# OpAmp_CH4.net
KiCad netlist of a schematic drawn in Altium Designer
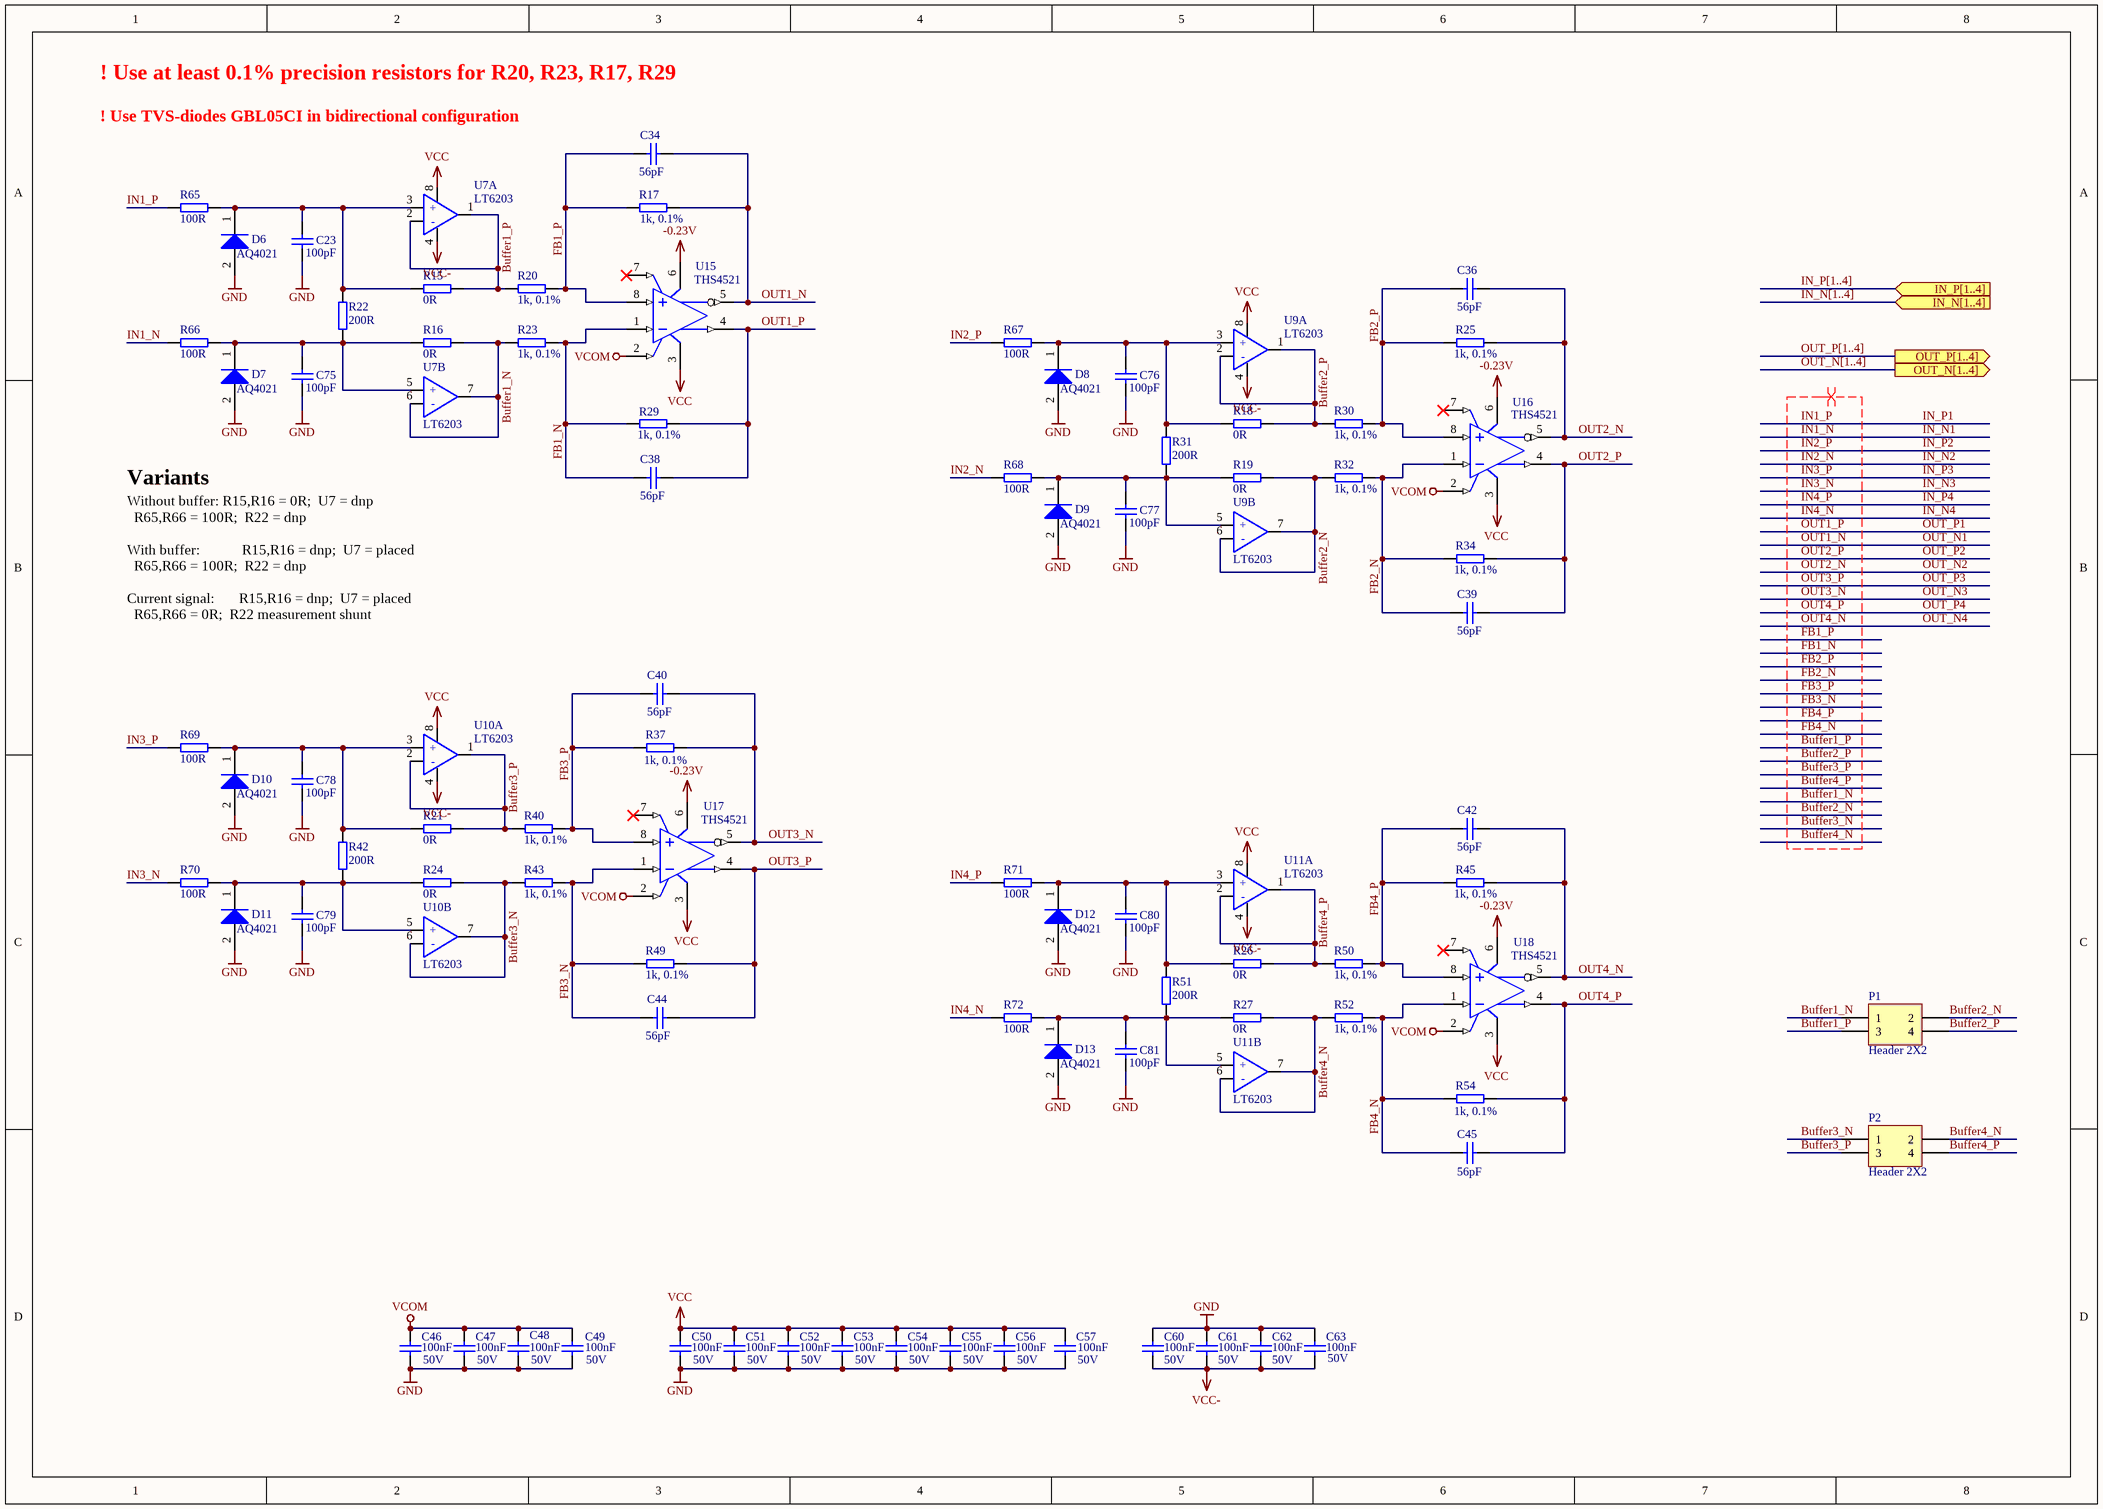
[diagram p0: OpAmp_CH4.SchDoc]

(export (version "E")
  (design (tool "Eeschema 10.0.6"))
  (components
    (comp (ref "C23")
      (value "100pF")
      (footprint "CAPC1608X07N")
      (fields
        (field (name "MF") "Würth Elektronik")
        (field (name "MPN") "885012006057")
        (field (name "VOLTAGE") "50V")
      )
      (libsource (lib "UltraZohm_ADC") (part "Cap_0603"))
    )
    (comp (ref "C34")
      (value "56pF")
      (footprint "CAPC1608X07N")
      (fields
        (field (name "MF") "Vishay")
        (field (name "MPN") "VJ0603A560JXACW1BC")
        (field (name "VOLTAGE") "50V")
      )
      (libsource (lib "UltraZohm_ADC") (part "Cap_0603"))
    )
    (comp (ref "C36")
      (value "56pF")
      (footprint "CAPC1608X07N")
      (fields
        (field (name "MF") "Vishay")
        (field (name "MPN") "VJ0603A560JXACW1BC")
        (field (name "VOLTAGE") "50V")
      )
      (libsource (lib "UltraZohm_ADC") (part "Cap_0603"))
    )
    (comp (ref "C38")
      (value "56pF")
      (footprint "CAPC1608X07N")
      (fields
        (field (name "MF") "Vishay")
        (field (name "MPN") "VJ0603A560JXACW1BC")
        (field (name "VOLTAGE") "50V")
      )
      (libsource (lib "UltraZohm_ADC") (part "Cap_0603"))
    )
    (comp (ref "C39")
      (value "56pF")
      (footprint "CAPC1608X07N")
      (fields
        (field (name "MF") "Vishay")
        (field (name "MPN") "VJ0603A560JXACW1BC")
        (field (name "VOLTAGE") "50V")
      )
      (libsource (lib "UltraZohm_ADC") (part "Cap_0603"))
    )
    (comp (ref "C40")
      (value "56pF")
      (footprint "CAPC1608X07N")
      (fields
        (field (name "MF") "Vishay")
        (field (name "MPN") "VJ0603A560JXACW1BC")
        (field (name "VOLTAGE") "50V")
      )
      (libsource (lib "UltraZohm_ADC") (part "Cap_0603"))
    )
    (comp (ref "C42")
      (value "56pF")
      (footprint "CAPC1608X07N")
      (fields
        (field (name "MF") "Vishay")
        (field (name "MPN") "VJ0603A560JXACW1BC")
        (field (name "VOLTAGE") "50V")
      )
      (libsource (lib "UltraZohm_ADC") (part "Cap_0603"))
    )
    (comp (ref "C44")
      (value "56pF")
      (footprint "CAPC1608X07N")
      (fields
        (field (name "MF") "Vishay")
        (field (name "MPN") "VJ0603A560JXACW1BC")
        (field (name "VOLTAGE") "50V")
      )
      (libsource (lib "UltraZohm_ADC") (part "Cap_0603"))
    )
    (comp (ref "C45")
      (value "56pF")
      (footprint "CAPC1608X07N")
      (fields
        (field (name "MF") "Vishay")
        (field (name "MPN") "VJ0603A560JXACW1BC")
        (field (name "VOLTAGE") "50V")
      )
      (libsource (lib "UltraZohm_ADC") (part "Cap_0603"))
    )
    (comp (ref "C46")
      (value "100nF")
      (footprint "CAPC1608X07N")
      (fields
        (field (name "MF") "Yageo")
        (field (name "MPN") "CC0603KRX7R9BB104")
        (field (name "VOLTAGE") "50V")
      )
      (libsource (lib "UltraZohm_ADC") (part "Cap_0603"))
    )
    (comp (ref "C47")
      (value "100nF")
      (footprint "CAPC1608X07N")
      (fields
        (field (name "MF") "Yageo")
        (field (name "MPN") "CC0603KRX7R9BB104")
        (field (name "VOLTAGE") "50V")
      )
      (libsource (lib "UltraZohm_ADC") (part "Cap_0603"))
    )
    (comp (ref "C48")
      (value "100nF")
      (footprint "CAPC1608X07N")
      (fields
        (field (name "MF") "Yageo")
        (field (name "MPN") "CC0603KRX7R9BB104")
        (field (name "VOLTAGE") "50V")
      )
      (libsource (lib "UltraZohm_ADC") (part "Cap_0603"))
    )
    (comp (ref "C49")
      (value "100nF")
      (footprint "CAPC1608X07N")
      (fields
        (field (name "MF") "Yageo")
        (field (name "MPN") "CC0603KRX7R9BB104")
        (field (name "VOLTAGE") "50V")
      )
      (libsource (lib "UltraZohm_ADC") (part "Cap_0603"))
    )
    (comp (ref "C50")
      (value "100nF")
      (footprint "CAPC1608X07N")
      (fields
        (field (name "MF") "Yageo")
        (field (name "MPN") "CC0603KRX7R9BB104")
        (field (name "VOLTAGE") "50V")
      )
      (libsource (lib "UltraZohm_ADC") (part "Cap_0603"))
    )
    (comp (ref "C51")
      (value "100nF")
      (footprint "CAPC1608X07N")
      (fields
        (field (name "MF") "Yageo")
        (field (name "MPN") "CC0603KRX7R9BB104")
        (field (name "VOLTAGE") "50V")
      )
      (libsource (lib "UltraZohm_ADC") (part "Cap_0603"))
    )
    (comp (ref "C52")
      (value "100nF")
      (footprint "CAPC1608X07N")
      (fields
        (field (name "MF") "Yageo")
        (field (name "MPN") "CC0603KRX7R9BB104")
        (field (name "VOLTAGE") "50V")
      )
      (libsource (lib "UltraZohm_ADC") (part "Cap_0603"))
    )
    (comp (ref "C53")
      (value "100nF")
      (footprint "CAPC1608X07N")
      (fields
        (field (name "MF") "Yageo")
        (field (name "MPN") "CC0603KRX7R9BB104")
        (field (name "VOLTAGE") "50V")
      )
      (libsource (lib "UltraZohm_ADC") (part "Cap_0603"))
    )
    (comp (ref "C54")
      (value "100nF")
      (footprint "CAPC1608X07N")
      (fields
        (field (name "MF") "Yageo")
        (field (name "MPN") "CC0603KRX7R9BB104")
        (field (name "VOLTAGE") "50V")
      )
      (libsource (lib "UltraZohm_ADC") (part "Cap_0603"))
    )
    (comp (ref "C55")
      (value "100nF")
      (footprint "CAPC1608X07N")
      (fields
        (field (name "MF") "Yageo")
        (field (name "MPN") "CC0603KRX7R9BB104")
        (field (name "VOLTAGE") "50V")
      )
      (libsource (lib "UltraZohm_ADC") (part "Cap_0603"))
    )
    (comp (ref "C56")
      (value "100nF")
      (footprint "CAPC1608X07N")
      (fields
        (field (name "MF") "Yageo")
        (field (name "MPN") "CC0603KRX7R9BB104")
        (field (name "VOLTAGE") "50V")
      )
      (libsource (lib "UltraZohm_ADC") (part "Cap_0603"))
    )
    (comp (ref "C57")
      (value "100nF")
      (footprint "CAPC1608X07N")
      (fields
        (field (name "MF") "Yageo")
        (field (name "MPN") "CC0603KRX7R9BB104")
        (field (name "VOLTAGE") "50V")
      )
      (libsource (lib "UltraZohm_ADC") (part "Cap_0603"))
    )
    (comp (ref "C60")
      (value "100nF")
      (footprint "CAPC1608X07N")
      (fields
        (field (name "MF") "Yageo")
        (field (name "MPN") "CC0603KRX7R9BB104")
        (field (name "VOLTAGE") "50V")
      )
      (libsource (lib "UltraZohm_ADC") (part "Cap_0603"))
    )
    (comp (ref "C61")
      (value "100nF")
      (footprint "CAPC1608X07N")
      (fields
        (field (name "MF") "Yageo")
        (field (name "MPN") "CC0603KRX7R9BB104")
        (field (name "VOLTAGE") "50V")
      )
      (libsource (lib "UltraZohm_ADC") (part "Cap_0603"))
    )
    (comp (ref "C62")
      (value "100nF")
      (footprint "CAPC1608X07N")
      (fields
        (field (name "MF") "Yageo")
        (field (name "MPN") "CC0603KRX7R9BB104")
        (field (name "VOLTAGE") "50V")
      )
      (libsource (lib "UltraZohm_ADC") (part "Cap_0603"))
    )
    (comp (ref "C63")
      (value "100nF")
      (footprint "CAPC1608X07N")
      (fields
        (field (name "MF") "Yageo")
        (field (name "MPN") "CC0603KRX7R9BB104")
        (field (name "VOLTAGE") "50V")
      )
      (libsource (lib "UltraZohm_ADC") (part "Cap_0603"))
    )
    (comp (ref "C75")
      (value "100pF")
      (footprint "CAPC1608X07N")
      (fields
        (field (name "MF") "Würth Elektronik")
        (field (name "MPN") "885012006057")
        (field (name "VOLTAGE") "50V")
      )
      (libsource (lib "UltraZohm_ADC") (part "Cap_0603"))
    )
    (comp (ref "C76")
      (value "100pF")
      (footprint "CAPC1608X07N")
      (fields
        (field (name "MF") "Würth Elektronik")
        (field (name "MPN") "885012006057")
        (field (name "VOLTAGE") "50V")
      )
      (libsource (lib "UltraZohm_ADC") (part "Cap_0603"))
    )
    (comp (ref "C77")
      (value "100pF")
      (footprint "CAPC1608X07N")
      (fields
        (field (name "MF") "Würth Elektronik")
        (field (name "MPN") "885012006057")
        (field (name "VOLTAGE") "50V")
      )
      (libsource (lib "UltraZohm_ADC") (part "Cap_0603"))
    )
    (comp (ref "C78")
      (value "100pF")
      (footprint "CAPC1608X07N")
      (fields
        (field (name "MF") "Würth Elektronik")
        (field (name "MPN") "885012006057")
        (field (name "VOLTAGE") "50V")
      )
      (libsource (lib "UltraZohm_ADC") (part "Cap_0603"))
    )
    (comp (ref "C79")
      (value "100pF")
      (footprint "CAPC1608X07N")
      (fields
        (field (name "MF") "Würth Elektronik")
        (field (name "MPN") "885012006057")
        (field (name "VOLTAGE") "50V")
      )
      (libsource (lib "UltraZohm_ADC") (part "Cap_0603"))
    )
    (comp (ref "C80")
      (value "100pF")
      (footprint "CAPC1608X07N")
      (fields
        (field (name "MF") "Würth Elektronik")
        (field (name "MPN") "885012006057")
        (field (name "VOLTAGE") "50V")
      )
      (libsource (lib "UltraZohm_ADC") (part "Cap_0603"))
    )
    (comp (ref "C81")
      (value "100pF")
      (footprint "CAPC1608X07N")
      (fields
        (field (name "MF") "Würth Elektronik")
        (field (name "MPN") "885012006057")
        (field (name "VOLTAGE") "50V")
      )
      (libsource (lib "UltraZohm_ADC") (part "Cap_0603"))
    )
    (comp (ref "D6")
      (value "AQ4021")
      (footprint "SOD-323_SuppressorDiode")
      (description "ESD Suppressor Diode TVS Bi-Dir 5V")
      (fields (field (name "MF") "Littelfuse") (field (name "MPN") "AQ4021-01FTG-C"))
      (libsource (lib "UltraZohm_ADC") (part "GBLCxx"))
    )
    (comp (ref "D7")
      (value "AQ4021")
      (footprint "SOD-323_SuppressorDiode")
      (description "ESD Suppressor Diode TVS Bi-Dir 5V")
      (fields (field (name "MF") "Littelfuse") (field (name "MPN") "AQ4021-01FTG-C"))
      (libsource (lib "UltraZohm_ADC") (part "GBLCxx"))
    )
    (comp (ref "D8")
      (value "AQ4021")
      (footprint "SOD-323_SuppressorDiode")
      (description "ESD Suppressor Diode TVS Bi-Dir 5V")
      (fields (field (name "MF") "Littelfuse") (field (name "MPN") "AQ4021-01FTG-C"))
      (libsource (lib "UltraZohm_ADC") (part "GBLCxx"))
    )
    (comp (ref "D9")
      (value "AQ4021")
      (footprint "SOD-323_SuppressorDiode")
      (description "ESD Suppressor Diode TVS Bi-Dir 5V")
      (fields (field (name "MF") "Littelfuse") (field (name "MPN") "AQ4021-01FTG-C"))
      (libsource (lib "UltraZohm_ADC") (part "GBLCxx"))
    )
    (comp (ref "D10")
      (value "AQ4021")
      (footprint "SOD-323_SuppressorDiode")
      (description "ESD Suppressor Diode TVS Bi-Dir 5V")
      (fields (field (name "MF") "Littelfuse") (field (name "MPN") "AQ4021-01FTG-C"))
      (libsource (lib "UltraZohm_ADC") (part "GBLCxx"))
    )
    (comp (ref "D11")
      (value "AQ4021")
      (footprint "SOD-323_SuppressorDiode")
      (description "ESD Suppressor Diode TVS Bi-Dir 5V")
      (fields (field (name "MF") "Littelfuse") (field (name "MPN") "AQ4021-01FTG-C"))
      (libsource (lib "UltraZohm_ADC") (part "GBLCxx"))
    )
    (comp (ref "D12")
      (value "AQ4021")
      (footprint "SOD-323_SuppressorDiode")
      (description "ESD Suppressor Diode TVS Bi-Dir 5V")
      (fields (field (name "MF") "Littelfuse") (field (name "MPN") "AQ4021-01FTG-C"))
      (libsource (lib "UltraZohm_ADC") (part "GBLCxx"))
    )
    (comp (ref "D13")
      (value "AQ4021")
      (footprint "SOD-323_SuppressorDiode")
      (description "ESD Suppressor Diode TVS Bi-Dir 5V")
      (fields (field (name "MF") "Littelfuse") (field (name "MPN") "AQ4021-01FTG-C"))
      (libsource (lib "UltraZohm_ADC") (part "GBLCxx"))
    )
    (comp (ref "P1")
      (value "Header 2X2")
      (footprint "HDR2X2")
      (description "Header, 2-Pin, Dual row")
      (fields (field (name "PUBLISHER") "Altium Limited"))
      (libsource (lib "Miscellaneous Connectors") (part "Header 2X2"))
    )
    (comp (ref "P2")
      (value "Header 2X2")
      (footprint "HDR2X2")
      (description "Header, 2-Pin, Dual row")
      (fields (field (name "PUBLISHER") "Altium Limited"))
      (libsource (lib "Miscellaneous Connectors") (part "Header 2X2"))
    )
    (comp (ref "R15")
      (value "0R")
      (footprint "RESC1608X06N")
      (fields (field (name "MF") "Vishay / Dale") (field (name "MPN") "CRCW06030000Z0EBC"))
      (libsource (lib "UltraZohm_ADC") (part "R_0603"))
    )
    (comp (ref "R16")
      (value "0R")
      (footprint "RESC1608X06N")
      (fields (field (name "MF") "Vishay / Dale") (field (name "MPN") "CRCW06030000Z0EBC"))
      (libsource (lib "UltraZohm_ADC") (part "R_0603"))
    )
    (comp (ref "R17")
      (value "1k, 0.1%")
      (footprint "RESC1608X06N")
      (description "Precision Resistor 1k 0.1% 0603")
      (fields (field (name "MF") "IRC/TT Electronics") (field (name "MPN") "PCF-W0603LF-03-1001-B-P-LT"))
      (libsource (lib "UltraZohm_ADC") (part "R_0603"))
    )
    (comp (ref "R18")
      (value "0R")
      (footprint "RESC1608X06N")
      (fields (field (name "MF") "Vishay / Dale") (field (name "MPN") "CRCW06030000Z0EBC"))
      (libsource (lib "UltraZohm_ADC") (part "R_0603"))
    )
    (comp (ref "R19")
      (value "0R")
      (footprint "RESC1608X06N")
      (fields (field (name "MF") "Vishay / Dale") (field (name "MPN") "CRCW06030000Z0EBC"))
      (libsource (lib "UltraZohm_ADC") (part "R_0603"))
    )
    (comp (ref "R20")
      (value "1k, 0.1%")
      (footprint "RESC1608X06N")
      (description "Precision Resistor 1k 0.1% 0603")
      (fields (field (name "MF") "IRC/TT Electronics") (field (name "MPN") "PCF-W0603LF-03-1001-B-P-LT"))
      (libsource (lib "UltraZohm_ADC") (part "R_0603"))
    )
    (comp (ref "R21")
      (value "0R")
      (footprint "RESC1608X06N")
      (fields (field (name "MF") "Vishay / Dale") (field (name "MPN") "CRCW06030000Z0EBC"))
      (libsource (lib "UltraZohm_ADC") (part "R_0603"))
    )
    (comp (ref "R22")
      (value "200R")
      (footprint "RESC3216X65N")
      (description "WID SMD 1M 5% 0,25W")
      (fields
        (field (name "TOLERANCE") "5%")
        (field (name "MF") "AECOL/Ohmite")
        (field (name "CREATED") "2018_07_20_AGeiger")
      )
      (libsource (lib "UltraZOhm_CarrierBoard") (part "R_1206"))
    )
    (comp (ref "R23")
      (value "1k, 0.1%")
      (footprint "RESC1608X06N")
      (description "Precision Resistor 1k 0.1% 0603")
      (fields (field (name "MF") "IRC/TT Electronics") (field (name "MPN") "PCF-W0603LF-03-1001-B-P-LT"))
      (libsource (lib "UltraZohm_ADC") (part "R_0603"))
    )
    (comp (ref "R24")
      (value "0R")
      (footprint "RESC1608X06N")
      (fields (field (name "MF") "Vishay / Dale") (field (name "MPN") "CRCW06030000Z0EBC"))
      (libsource (lib "UltraZohm_ADC") (part "R_0603"))
    )
    (comp (ref "R25")
      (value "1k, 0.1%")
      (footprint "RESC1608X06N")
      (description "Precision Resistor 1k 0.1% 0603")
      (fields (field (name "MF") "IRC/TT Electronics") (field (name "MPN") "PCF-W0603LF-03-1001-B-P-LT"))
      (libsource (lib "UltraZohm_ADC") (part "R_0603"))
    )
    (comp (ref "R26")
      (value "0R")
      (footprint "RESC1608X06N")
      (fields (field (name "MF") "Vishay / Dale") (field (name "MPN") "CRCW06030000Z0EBC"))
      (libsource (lib "UltraZohm_ADC") (part "R_0603"))
    )
    (comp (ref "R27")
      (value "0R")
      (footprint "RESC1608X06N")
      (fields (field (name "MF") "Vishay / Dale") (field (name "MPN") "CRCW06030000Z0EBC"))
      (libsource (lib "UltraZohm_ADC") (part "R_0603"))
    )
    (comp (ref "R29")
      (value "1k, 0.1%")
      (footprint "RESC1608X06N")
      (description "Precision Resistor 1k 0.1% 0603")
      (fields (field (name "MF") "IRC/TT Electronics") (field (name "MPN") "PCF-W0603LF-03-1001-B-P-LT"))
      (libsource (lib "UltraZohm_ADC") (part "R_0603"))
    )
    (comp (ref "R30")
      (value "1k, 0.1%")
      (footprint "RESC1608X06N")
      (description "Precision Resistor 1k 0.1% 0603")
      (fields (field (name "MF") "IRC/TT Electronics") (field (name "MPN") "PCF-W0603LF-03-1001-B-P-LT"))
      (libsource (lib "UltraZohm_ADC") (part "R_0603"))
    )
    (comp (ref "R31")
      (value "200R")
      (footprint "RESC3216X65N")
      (description "WID SMD 1M 5% 0,25W")
      (fields
        (field (name "TOLERANCE") "5%")
        (field (name "MF") "AECOL/Ohmite")
        (field (name "CREATED") "2018_07_20_AGeiger")
      )
      (libsource (lib "UltraZOhm_CarrierBoard") (part "R_1206"))
    )
    (comp (ref "R32")
      (value "1k, 0.1%")
      (footprint "RESC1608X06N")
      (description "Precision Resistor 1k 0.1% 0603")
      (fields (field (name "MF") "IRC/TT Electronics") (field (name "MPN") "PCF-W0603LF-03-1001-B-P-LT"))
      (libsource (lib "UltraZohm_ADC") (part "R_0603"))
    )
    (comp (ref "R34")
      (value "1k, 0.1%")
      (footprint "RESC1608X06N")
      (description "Precision Resistor 1k 0.1% 0603")
      (fields (field (name "MF") "IRC/TT Electronics") (field (name "MPN") "PCF-W0603LF-03-1001-B-P-LT"))
      (libsource (lib "UltraZohm_ADC") (part "R_0603"))
    )
    (comp (ref "R37")
      (value "1k, 0.1%")
      (footprint "RESC1608X06N")
      (description "Precision Resistor 1k 0.1% 0603")
      (fields (field (name "MF") "IRC/TT Electronics") (field (name "MPN") "PCF-W0603LF-03-1001-B-P-LT"))
      (libsource (lib "UltraZohm_ADC") (part "R_0603"))
    )
    (comp (ref "R40")
      (value "1k, 0.1%")
      (footprint "RESC1608X06N")
      (description "Precision Resistor 1k 0.1% 0603")
      (fields (field (name "MF") "IRC/TT Electronics") (field (name "MPN") "PCF-W0603LF-03-1001-B-P-LT"))
      (libsource (lib "UltraZohm_ADC") (part "R_0603"))
    )
    (comp (ref "R42")
      (value "200R")
      (footprint "RESC3216X65N")
      (description "WID SMD 1M 5% 0,25W")
      (fields
        (field (name "TOLERANCE") "5%")
        (field (name "MF") "AECOL/Ohmite")
        (field (name "CREATED") "2018_07_20_AGeiger")
      )
      (libsource (lib "UltraZOhm_CarrierBoard") (part "R_1206"))
    )
    (comp (ref "R43")
      (value "1k, 0.1%")
      (footprint "RESC1608X06N")
      (description "Precision Resistor 1k 0.1% 0603")
      (fields (field (name "MF") "IRC/TT Electronics") (field (name "MPN") "PCF-W0603LF-03-1001-B-P-LT"))
      (libsource (lib "UltraZohm_ADC") (part "R_0805"))
    )
    (comp (ref "R45")
      (value "1k, 0.1%")
      (footprint "RESC1608X06N")
      (description "Precision Resistor 1k 0.1% 0603")
      (fields (field (name "MF") "IRC/TT Electronics") (field (name "MPN") "PCF-W0603LF-03-1001-B-P-LT"))
      (libsource (lib "UltraZohm_ADC") (part "R_0603"))
    )
    (comp (ref "R49")
      (value "1k, 0.1%")
      (footprint "RESC1608X06N")
      (description "Precision Resistor 1k 0.1% 0603")
      (fields (field (name "MF") "IRC/TT Electronics") (field (name "MPN") "PCF-W0603LF-03-1001-B-P-LT"))
      (libsource (lib "UltraZohm_ADC") (part "R_0603"))
    )
    (comp (ref "R50")
      (value "1k, 0.1%")
      (footprint "RESC1608X06N")
      (description "Precision Resistor 1k 0.1% 0603")
      (fields (field (name "MF") "IRC/TT Electronics") (field (name "MPN") "PCF-W0603LF-03-1001-B-P-LT"))
      (libsource (lib "UltraZohm_ADC") (part "R_0603"))
    )
    (comp (ref "R51")
      (value "200R")
      (footprint "RESC3216X65N")
      (description "WID SMD 1M 5% 0,25W")
      (fields
        (field (name "TOLERANCE") "5%")
        (field (name "MF") "AECOL/Ohmite")
        (field (name "CREATED") "2018_07_20_AGeiger")
      )
      (libsource (lib "UltraZOhm_CarrierBoard") (part "R_1206"))
    )
    (comp (ref "R52")
      (value "1k, 0.1%")
      (footprint "RESC1608X06N")
      (description "Precision Resistor 1k 0.1% 0603")
      (fields (field (name "MF") "IRC/TT Electronics") (field (name "MPN") "PCF-W0603LF-03-1001-B-P-LT"))
      (libsource (lib "UltraZohm_ADC") (part "R_0603"))
    )
    (comp (ref "R54")
      (value "1k, 0.1%")
      (footprint "RESC1608X06N")
      (description "Precision Resistor 1k 0.1% 0603")
      (fields (field (name "MF") "IRC/TT Electronics") (field (name "MPN") "PCF-W0603LF-03-1001-B-P-LT"))
      (libsource (lib "UltraZohm_ADC") (part "R_0603"))
    )
    (comp (ref "R65")
      (value "100R")
      (footprint "RESC1608X06N")
      (fields
        (field (name "MF") "Yageo")
        (field (name "MPN") "AC0603FR-13100RL")
        (field (name "TOLERANCE") "1%")
      )
      (libsource (lib "UltraZohm_ADC") (part "R_0603"))
    )
    (comp (ref "R66")
      (value "100R")
      (footprint "RESC1608X06N")
      (fields
        (field (name "MF") "Yageo")
        (field (name "MPN") "AC0603FR-13100RL")
        (field (name "TOLERANCE") "1%")
      )
      (libsource (lib "UltraZohm_ADC") (part "R_0603"))
    )
    (comp (ref "R67")
      (value "100R")
      (footprint "RESC1608X06N")
      (fields
        (field (name "MF") "Yageo")
        (field (name "MPN") "AC0603FR-13100RL")
        (field (name "TOLERANCE") "1%")
      )
      (libsource (lib "UltraZohm_ADC") (part "R_0603"))
    )
    (comp (ref "R68")
      (value "100R")
      (footprint "RESC1608X06N")
      (fields
        (field (name "MF") "Yageo")
        (field (name "MPN") "AC0603FR-13100RL")
        (field (name "TOLERANCE") "1%")
      )
      (libsource (lib "UltraZohm_ADC") (part "R_0603"))
    )
    (comp (ref "R69")
      (value "100R")
      (footprint "RESC1608X06N")
      (fields
        (field (name "MF") "Yageo")
        (field (name "MPN") "AC0603FR-13100RL")
        (field (name "TOLERANCE") "1%")
      )
      (libsource (lib "UltraZohm_ADC") (part "R_0603"))
    )
    (comp (ref "R70")
      (value "100R")
      (footprint "RESC1608X06N")
      (fields
        (field (name "MF") "Yageo")
        (field (name "MPN") "AC0603FR-13100RL")
        (field (name "TOLERANCE") "1%")
      )
      (libsource (lib "UltraZohm_ADC") (part "R_0603"))
    )
    (comp (ref "R71")
      (value "100R")
      (footprint "RESC1608X06N")
      (fields
        (field (name "MF") "Yageo")
        (field (name "MPN") "AC0603FR-13100RL")
        (field (name "TOLERANCE") "1%")
      )
      (libsource (lib "UltraZohm_ADC") (part "R_0603"))
    )
    (comp (ref "R72")
      (value "100R")
      (footprint "RESC1608X06N")
      (fields
        (field (name "MF") "Yageo")
        (field (name "MPN") "AC0603FR-13100RL")
        (field (name "TOLERANCE") "1%")
      )
      (libsource (lib "UltraZohm_ADC") (part "R_0603"))
    )
    (comp (ref "U7")
      (value "LT6203")
      (footprint "MSOP8_3x3-8N")
      (description "2 Ch Low Noise, Low Power OpAmp")
      (fields
        (field (name "MF") "Linear Technology")
        (field (name "MPN") "LT6203CMS8#PBF")
        (field (name "CREATED") "Kreppel_20190830")
      )
      (libsource (lib "UltraZohm_ADC") (part "LT6203_MSOP8"))
    )
    (comp (ref "U9")
      (value "LT6203")
      (footprint "MSOP8_3x3-8N")
      (description "2 Ch Low Noise, Low Power OpAmp")
      (fields
        (field (name "MF") "Linear Technology")
        (field (name "MPN") "LT6203CMS8#PBF")
        (field (name "CREATED") "Kreppel_20190830")
      )
      (libsource (lib "UltraZohm_ADC") (part "LT6203_MSOP8"))
    )
    (comp (ref "U10")
      (value "LT6203")
      (footprint "MSOP8_3x3-8N")
      (description "2 Ch Low Noise, Low Power OpAmp")
      (fields
        (field (name "MF") "Linear Technology")
        (field (name "MPN") "LT6203CMS8#PBF")
        (field (name "CREATED") "Kreppel_20190830")
      )
      (libsource (lib "UltraZohm_ADC") (part "LT6203_MSOP8"))
    )
    (comp (ref "U11")
      (value "LT6203")
      (footprint "MSOP8_3x3-8N")
      (description "2 Ch Low Noise, Low Power OpAmp")
      (fields
        (field (name "MF") "Linear Technology")
        (field (name "MPN") "LT6203CMS8#PBF")
        (field (name "CREATED") "Kreppel_20190830")
      )
      (libsource (lib "UltraZohm_ADC") (part "LT6203_MSOP8"))
    )
    (comp (ref "U15")
      (value "THS4521")
      (footprint "DGK0008A_N")
      (description "IC AMP RRO NEG OUT VLP 8VSSOP (Single Channel fully differential Amplifier)")
      (fields
        (field (name "MANUFACTURER") "Texas Instruments")
        (field (name "MANUFACTURER PART NUMBER") "THS4521IDGKR")
      )
      (libsource (lib "UltraZohm_ADC") (part "THS4521IDGKR"))
    )
    (comp (ref "U16")
      (value "THS4521")
      (footprint "DGK0008A_N")
      (description "IC AMP RRO NEG OUT VLP 8VSSOP (Single Channel fully differential Amplifier)")
      (fields
        (field (name "MANUFACTURER") "Texas Instruments")
        (field (name "MANUFACTURER PART NUMBER") "THS4521IDGKR")
      )
      (libsource (lib "UltraZohm_ADC") (part "THS4521IDGKR"))
    )
    (comp (ref "U17")
      (value "THS4521")
      (footprint "DGK0008A_N")
      (description "IC AMP RRO NEG OUT VLP 8VSSOP (Single Channel fully differential Amplifier)")
      (fields
        (field (name "MANUFACTURER") "Texas Instruments")
        (field (name "MANUFACTURER PART NUMBER") "THS4521IDGKR")
      )
      (libsource (lib "UltraZohm_ADC") (part "THS4521IDGKR"))
    )
    (comp (ref "U18")
      (value "THS4521")
      (footprint "DGK0008A_N")
      (description "IC AMP RRO NEG OUT VLP 8VSSOP (Single Channel fully differential Amplifier)")
      (fields
        (field (name "MANUFACTURER") "Texas Instruments")
        (field (name "MANUFACTURER PART NUMBER") "THS4521IDGKR")
      )
      (libsource (lib "UltraZohm_ADC") (part "THS4521IDGKR"))
    )
  )
  (nets
    (net (code "1") (name "-0.23V") (class "Default")
      (node (ref "U15") (pin "6") (pinfunction "VS-_6") (pintype "power_in"))
      (node (ref "U16") (pin "6") (pinfunction "VS-_6") (pintype "power_in"))
      (node (ref "U17") (pin "6") (pinfunction "VS-_6") (pintype "power_in"))
      (node (ref "U18") (pin "6") (pinfunction "VS-_6") (pintype "power_in"))
    )
    (net (code "2") (name "/Buffer1_N") (class "Default")
      (node (ref "P1") (pin "1") (pinfunction "1_1") (pintype "passive"))
      (node (ref "R16") (pin "2") (pintype "passive"))
      (node (ref "R23") (pin "2") (pintype "passive"))
      (node (ref "U7") (pin "6") (pinfunction "-_6") (pintype "passive"))
      (node (ref "U7") (pin "7") (pintype "passive"))
    )
    (net (code "3") (name "/Buffer1_P") (class "Default")
      (node (ref "P1") (pin "3") (pinfunction "3_3") (pintype "passive"))
      (node (ref "R15") (pin "2") (pintype "passive"))
      (node (ref "R20") (pin "1") (pintype "passive"))
      (node (ref "U7") (pin "1") (pintype "passive"))
      (node (ref "U7") (pin "2") (pinfunction "-_2") (pintype "passive"))
    )
    (net (code "4") (name "/Buffer2_N") (class "Default")
      (node (ref "P1") (pin "2") (pinfunction "2_2") (pintype "passive"))
      (node (ref "R19") (pin "2") (pintype "passive"))
      (node (ref "R32") (pin "2") (pintype "passive"))
      (node (ref "U9") (pin "6") (pinfunction "-_6") (pintype "passive"))
      (node (ref "U9") (pin "7") (pintype "passive"))
    )
    (net (code "5") (name "/Buffer2_P") (class "Default")
      (node (ref "P1") (pin "4") (pinfunction "4_4") (pintype "passive"))
      (node (ref "R18") (pin "2") (pintype "passive"))
      (node (ref "R30") (pin "1") (pintype "passive"))
      (node (ref "U9") (pin "1") (pintype "passive"))
      (node (ref "U9") (pin "2") (pinfunction "-_2") (pintype "passive"))
    )
    (net (code "6") (name "/Buffer3_N") (class "Default")
      (node (ref "P2") (pin "1") (pinfunction "1_1") (pintype "passive"))
      (node (ref "R24") (pin "2") (pintype "passive"))
      (node (ref "R43") (pin "2") (pintype "passive"))
      (node (ref "U10") (pin "6") (pinfunction "-_6") (pintype "passive"))
      (node (ref "U10") (pin "7") (pintype "passive"))
    )
    (net (code "7") (name "/Buffer3_P") (class "Default")
      (node (ref "P2") (pin "3") (pinfunction "3_3") (pintype "passive"))
      (node (ref "R21") (pin "2") (pintype "passive"))
      (node (ref "R40") (pin "1") (pintype "passive"))
      (node (ref "U10") (pin "1") (pintype "passive"))
      (node (ref "U10") (pin "2") (pinfunction "-_2") (pintype "passive"))
    )
    (net (code "8") (name "/Buffer4_N") (class "Default")
      (node (ref "P2") (pin "2") (pinfunction "2_2") (pintype "passive"))
      (node (ref "R27") (pin "2") (pintype "passive"))
      (node (ref "R52") (pin "2") (pintype "passive"))
      (node (ref "U11") (pin "6") (pinfunction "-_6") (pintype "passive"))
      (node (ref "U11") (pin "7") (pintype "passive"))
    )
    (net (code "9") (name "/Buffer4_P") (class "Default")
      (node (ref "P2") (pin "4") (pinfunction "4_4") (pintype "passive"))
      (node (ref "R26") (pin "2") (pintype "passive"))
      (node (ref "R50") (pin "1") (pintype "passive"))
      (node (ref "U11") (pin "1") (pintype "passive"))
      (node (ref "U11") (pin "2") (pinfunction "-_2") (pintype "passive"))
    )
    (net (code "10") (name "/FB1_N") (class "Default")
      (node (ref "C38") (pin "1") (pinfunction "1_1") (pintype "passive"))
      (node (ref "R23") (pin "1") (pintype "passive"))
      (node (ref "R29") (pin "1") (pintype "passive"))
      (node (ref "U15") (pin "1") (pinfunction "VIN-_1") (pintype "input"))
    )
    (net (code "11") (name "/FB1_P") (class "Default")
      (node (ref "C34") (pin "1") (pinfunction "1_1") (pintype "passive"))
      (node (ref "R17") (pin "1") (pintype "passive"))
      (node (ref "R20") (pin "2") (pintype "passive"))
      (node (ref "U15") (pin "8") (pinfunction "VIN+_8") (pintype "input"))
    )
    (net (code "12") (name "/FB2_N") (class "Default")
      (node (ref "C39") (pin "1") (pinfunction "1_1") (pintype "passive"))
      (node (ref "R32") (pin "1") (pintype "passive"))
      (node (ref "R34") (pin "1") (pintype "passive"))
      (node (ref "U16") (pin "1") (pinfunction "VIN-_1") (pintype "input"))
    )
    (net (code "13") (name "/FB2_P") (class "Default")
      (node (ref "C36") (pin "1") (pinfunction "1_1") (pintype "passive"))
      (node (ref "R25") (pin "1") (pintype "passive"))
      (node (ref "R30") (pin "2") (pintype "passive"))
      (node (ref "U16") (pin "8") (pinfunction "VIN+_8") (pintype "input"))
    )
    (net (code "14") (name "/FB3_N") (class "Default")
      (node (ref "C44") (pin "1") (pinfunction "1_1") (pintype "passive"))
      (node (ref "R43") (pin "1") (pintype "passive"))
      (node (ref "R49") (pin "1") (pintype "passive"))
      (node (ref "U17") (pin "1") (pinfunction "VIN-_1") (pintype "input"))
    )
    (net (code "15") (name "/FB3_P") (class "Default")
      (node (ref "C40") (pin "1") (pinfunction "1_1") (pintype "passive"))
      (node (ref "R37") (pin "1") (pintype "passive"))
      (node (ref "R40") (pin "2") (pintype "passive"))
      (node (ref "U17") (pin "8") (pinfunction "VIN+_8") (pintype "input"))
    )
    (net (code "16") (name "/FB4_N") (class "Default")
      (node (ref "C45") (pin "1") (pinfunction "1_1") (pintype "passive"))
      (node (ref "R52") (pin "1") (pintype "passive"))
      (node (ref "R54") (pin "1") (pintype "passive"))
      (node (ref "U18") (pin "1") (pinfunction "VIN-_1") (pintype "input"))
    )
    (net (code "17") (name "/FB4_P") (class "Default")
      (node (ref "C42") (pin "1") (pinfunction "1_1") (pintype "passive"))
      (node (ref "R45") (pin "1") (pintype "passive"))
      (node (ref "R50") (pin "2") (pintype "passive"))
      (node (ref "U18") (pin "8") (pinfunction "VIN+_8") (pintype "input"))
    )
    (net (code "18") (name "/IN_N1") (class "Default") (node (ref "R66") (pin "1") (pintype "passive")))
    (net (code "19") (name "/IN_N2") (class "Default") (node (ref "R68") (pin "1") (pintype "passive")))
    (net (code "20") (name "/IN_N3") (class "Default") (node (ref "R70") (pin "1") (pintype "passive")))
    (net (code "21") (name "/IN_N4") (class "Default") (node (ref "R72") (pin "1") (pintype "passive")))
    (net (code "23") (name "/IN_P1") (class "Default") (node (ref "R65") (pin "1") (pintype "passive")))
    (net (code "24") (name "/IN_P2") (class "Default") (node (ref "R67") (pin "1") (pintype "passive")))
    (net (code "25") (name "/IN_P3") (class "Default") (node (ref "R69") (pin "1") (pintype "passive")))
    (net (code "26") (name "/IN_P4") (class "Default") (node (ref "R71") (pin "1") (pintype "passive")))
    (net (code "28") (name "/OUT_N1") (class "Default")
      (node (ref "C34") (pin "2") (pinfunction "2_2") (pintype "passive"))
      (node (ref "R17") (pin "2") (pintype "passive"))
      (node (ref "U15") (pin "5") (pinfunction "VOUT-_5") (pintype "output"))
    )
    (net (code "29") (name "/OUT_N2") (class "Default")
      (node (ref "C36") (pin "2") (pinfunction "2_2") (pintype "passive"))
      (node (ref "R25") (pin "2") (pintype "passive"))
      (node (ref "U16") (pin "5") (pinfunction "VOUT-_5") (pintype "output"))
    )
    (net (code "30") (name "/OUT_N3") (class "Default")
      (node (ref "C40") (pin "2") (pinfunction "2_2") (pintype "passive"))
      (node (ref "R37") (pin "2") (pintype "passive"))
      (node (ref "U17") (pin "5") (pinfunction "VOUT-_5") (pintype "output"))
    )
    (net (code "31") (name "/OUT_N4") (class "Default")
      (node (ref "C42") (pin "2") (pinfunction "2_2") (pintype "passive"))
      (node (ref "R45") (pin "2") (pintype "passive"))
      (node (ref "U18") (pin "5") (pinfunction "VOUT-_5") (pintype "output"))
    )
    (net (code "33") (name "/OUT_P1") (class "Default")
      (node (ref "C38") (pin "2") (pinfunction "2_2") (pintype "passive"))
      (node (ref "R29") (pin "2") (pintype "passive"))
      (node (ref "U15") (pin "4") (pinfunction "VOUT+_4") (pintype "output"))
    )
    (net (code "34") (name "/OUT_P2") (class "Default")
      (node (ref "C39") (pin "2") (pinfunction "2_2") (pintype "passive"))
      (node (ref "R34") (pin "2") (pintype "passive"))
      (node (ref "U16") (pin "4") (pinfunction "VOUT+_4") (pintype "output"))
    )
    (net (code "35") (name "/OUT_P3") (class "Default")
      (node (ref "C44") (pin "2") (pinfunction "2_2") (pintype "passive"))
      (node (ref "R49") (pin "2") (pintype "passive"))
      (node (ref "U17") (pin "4") (pinfunction "VOUT+_4") (pintype "output"))
    )
    (net (code "36") (name "/OUT_P4") (class "Default")
      (node (ref "C45") (pin "2") (pinfunction "2_2") (pintype "passive"))
      (node (ref "R54") (pin "2") (pintype "passive"))
      (node (ref "U18") (pin "4") (pinfunction "VOUT+_4") (pintype "output"))
    )
    (net (code "38") (name "GND") (class "Default")
      (node (ref "C23") (pin "2") (pinfunction "2_2") (pintype "passive"))
      (node (ref "C46") (pin "2") (pinfunction "2_2") (pintype "passive"))
      (node (ref "C47") (pin "2") (pinfunction "2_2") (pintype "passive"))
      (node (ref "C48") (pin "2") (pinfunction "2_2") (pintype "passive"))
      (node (ref "C49") (pin "2") (pinfunction "2_2") (pintype "passive"))
      (node (ref "C50") (pin "2") (pinfunction "2_2") (pintype "passive"))
      (node (ref "C51") (pin "2") (pinfunction "2_2") (pintype "passive"))
      (node (ref "C52") (pin "2") (pinfunction "2_2") (pintype "passive"))
      (node (ref "C53") (pin "2") (pinfunction "2_2") (pintype "passive"))
      (node (ref "C54") (pin "2") (pinfunction "2_2") (pintype "passive"))
      (node (ref "C55") (pin "2") (pinfunction "2_2") (pintype "passive"))
      (node (ref "C56") (pin "2") (pinfunction "2_2") (pintype "passive"))
      (node (ref "C57") (pin "2") (pinfunction "2_2") (pintype "passive"))
      (node (ref "C60") (pin "1") (pinfunction "1_1") (pintype "passive"))
      (node (ref "C61") (pin "1") (pinfunction "1_1") (pintype "passive"))
      (node (ref "C62") (pin "1") (pinfunction "1_1") (pintype "passive"))
      (node (ref "C63") (pin "1") (pinfunction "1_1") (pintype "passive"))
      (node (ref "C75") (pin "2") (pinfunction "2_2") (pintype "passive"))
      (node (ref "C76") (pin "2") (pinfunction "2_2") (pintype "passive"))
      (node (ref "C77") (pin "2") (pinfunction "2_2") (pintype "passive"))
      (node (ref "C78") (pin "2") (pinfunction "2_2") (pintype "passive"))
      (node (ref "C79") (pin "2") (pinfunction "2_2") (pintype "passive"))
      (node (ref "C80") (pin "2") (pinfunction "2_2") (pintype "passive"))
      (node (ref "C81") (pin "2") (pinfunction "2_2") (pintype "passive"))
      (node (ref "D10") (pin "2") (pinfunction "A_2") (pintype "passive"))
      (node (ref "D11") (pin "2") (pinfunction "A_2") (pintype "passive"))
      (node (ref "D12") (pin "2") (pinfunction "A_2") (pintype "passive"))
      (node (ref "D13") (pin "2") (pinfunction "A_2") (pintype "passive"))
      (node (ref "D6") (pin "2") (pinfunction "A_2") (pintype "passive"))
      (node (ref "D7") (pin "2") (pinfunction "A_2") (pintype "passive"))
      (node (ref "D8") (pin "2") (pinfunction "A_2") (pintype "passive"))
      (node (ref "D9") (pin "2") (pinfunction "A_2") (pintype "passive"))
    )
    (net (code "39") (name "Net-(D6-K)") (class "Default")
      (node (ref "C23") (pin "1") (pinfunction "1_1") (pintype "passive"))
      (node (ref "D6") (pin "1") (pinfunction "K_1") (pintype "passive"))
      (node (ref "R15") (pin "1") (pintype "passive"))
      (node (ref "R22") (pin "2") (pinfunction "2_2") (pintype "passive"))
      (node (ref "R65") (pin "2") (pintype "passive"))
      (node (ref "U7") (pin "3") (pinfunction "+_3") (pintype "passive"))
    )
    (net (code "40") (name "Net-(D7-K)") (class "Default")
      (node (ref "C75") (pin "1") (pinfunction "1_1") (pintype "passive"))
      (node (ref "D7") (pin "1") (pinfunction "K_1") (pintype "passive"))
      (node (ref "R16") (pin "1") (pintype "passive"))
      (node (ref "R22") (pin "1") (pinfunction "1_1") (pintype "passive"))
      (node (ref "R66") (pin "2") (pintype "passive"))
      (node (ref "U7") (pin "5") (pinfunction "+_5") (pintype "passive"))
    )
    (net (code "41") (name "Net-(D8-K)") (class "Default")
      (node (ref "C76") (pin "1") (pinfunction "1_1") (pintype "passive"))
      (node (ref "D8") (pin "1") (pinfunction "K_1") (pintype "passive"))
      (node (ref "R18") (pin "1") (pintype "passive"))
      (node (ref "R31") (pin "2") (pinfunction "2_2") (pintype "passive"))
      (node (ref "R67") (pin "2") (pintype "passive"))
      (node (ref "U9") (pin "3") (pinfunction "+_3") (pintype "passive"))
    )
    (net (code "42") (name "Net-(D9-K)") (class "Default")
      (node (ref "C77") (pin "1") (pinfunction "1_1") (pintype "passive"))
      (node (ref "D9") (pin "1") (pinfunction "K_1") (pintype "passive"))
      (node (ref "R19") (pin "1") (pintype "passive"))
      (node (ref "R31") (pin "1") (pinfunction "1_1") (pintype "passive"))
      (node (ref "R68") (pin "2") (pintype "passive"))
      (node (ref "U9") (pin "5") (pinfunction "+_5") (pintype "passive"))
    )
    (net (code "43") (name "Net-(D10-K)") (class "Default")
      (node (ref "C78") (pin "1") (pinfunction "1_1") (pintype "passive"))
      (node (ref "D10") (pin "1") (pinfunction "K_1") (pintype "passive"))
      (node (ref "R21") (pin "1") (pintype "passive"))
      (node (ref "R42") (pin "2") (pinfunction "2_2") (pintype "passive"))
      (node (ref "R69") (pin "2") (pintype "passive"))
      (node (ref "U10") (pin "3") (pinfunction "+_3") (pintype "passive"))
    )
    (net (code "44") (name "Net-(D11-K)") (class "Default")
      (node (ref "C79") (pin "1") (pinfunction "1_1") (pintype "passive"))
      (node (ref "D11") (pin "1") (pinfunction "K_1") (pintype "passive"))
      (node (ref "R24") (pin "1") (pintype "passive"))
      (node (ref "R42") (pin "1") (pinfunction "1_1") (pintype "passive"))
      (node (ref "R70") (pin "2") (pintype "passive"))
      (node (ref "U10") (pin "5") (pinfunction "+_5") (pintype "passive"))
    )
    (net (code "45") (name "Net-(D12-K)") (class "Default")
      (node (ref "C80") (pin "1") (pinfunction "1_1") (pintype "passive"))
      (node (ref "D12") (pin "1") (pinfunction "K_1") (pintype "passive"))
      (node (ref "R26") (pin "1") (pintype "passive"))
      (node (ref "R51") (pin "2") (pinfunction "2_2") (pintype "passive"))
      (node (ref "R71") (pin "2") (pintype "passive"))
      (node (ref "U11") (pin "3") (pinfunction "+_3") (pintype "passive"))
    )
    (net (code "46") (name "Net-(D13-K)") (class "Default")
      (node (ref "C81") (pin "1") (pinfunction "1_1") (pintype "passive"))
      (node (ref "D13") (pin "1") (pinfunction "K_1") (pintype "passive"))
      (node (ref "R27") (pin "1") (pintype "passive"))
      (node (ref "R51") (pin "1") (pinfunction "1_1") (pintype "passive"))
      (node (ref "R72") (pin "2") (pintype "passive"))
      (node (ref "U11") (pin "5") (pinfunction "+_5") (pintype "passive"))
    )
    (net (code "47") (name "VCC") (class "Default")
      (node (ref "C50") (pin "1") (pinfunction "1_1") (pintype "passive"))
      (node (ref "C51") (pin "1") (pinfunction "1_1") (pintype "passive"))
      (node (ref "C52") (pin "1") (pinfunction "1_1") (pintype "passive"))
      (node (ref "C53") (pin "1") (pinfunction "1_1") (pintype "passive"))
      (node (ref "C54") (pin "1") (pinfunction "1_1") (pintype "passive"))
      (node (ref "C55") (pin "1") (pinfunction "1_1") (pintype "passive"))
      (node (ref "C56") (pin "1") (pinfunction "1_1") (pintype "passive"))
      (node (ref "C57") (pin "1") (pinfunction "1_1") (pintype "passive"))
      (node (ref "U10") (pin "8") (pintype "passive"))
      (node (ref "U11") (pin "8") (pintype "passive"))
      (node (ref "U15") (pin "3") (pinfunction "VS+_3") (pintype "power_in"))
      (node (ref "U16") (pin "3") (pinfunction "VS+_3") (pintype "power_in"))
      (node (ref "U17") (pin "3") (pinfunction "VS+_3") (pintype "power_in"))
      (node (ref "U18") (pin "3") (pinfunction "VS+_3") (pintype "power_in"))
      (node (ref "U7") (pin "8") (pintype "passive"))
      (node (ref "U9") (pin "8") (pintype "passive"))
    )
    (net (code "48") (name "VCC-") (class "Default")
      (node (ref "C60") (pin "2") (pinfunction "2_2") (pintype "passive"))
      (node (ref "C61") (pin "2") (pinfunction "2_2") (pintype "passive"))
      (node (ref "C62") (pin "2") (pinfunction "2_2") (pintype "passive"))
      (node (ref "C63") (pin "2") (pinfunction "2_2") (pintype "passive"))
      (node (ref "U10") (pin "4") (pintype "passive"))
      (node (ref "U11") (pin "4") (pintype "passive"))
      (node (ref "U7") (pin "4") (pintype "passive"))
      (node (ref "U9") (pin "4") (pintype "passive"))
    )
    (net (code "49") (name "VCOM") (class "Default")
      (node (ref "C46") (pin "1") (pinfunction "1_1") (pintype "passive"))
      (node (ref "C47") (pin "1") (pinfunction "1_1") (pintype "passive"))
      (node (ref "C48") (pin "1") (pinfunction "1_1") (pintype "passive"))
      (node (ref "C49") (pin "1") (pinfunction "1_1") (pintype "passive"))
      (node (ref "U15") (pin "2") (pinfunction "VOCM_2") (pintype "input"))
      (node (ref "U16") (pin "2") (pinfunction "VOCM_2") (pintype "input"))
      (node (ref "U17") (pin "2") (pinfunction "VOCM_2") (pintype "input"))
      (node (ref "U18") (pin "2") (pinfunction "VOCM_2") (pintype "input"))
    )
    (net (code "50") (name "unconnected-(U15-~{PD}-Pad7)") (class "Default")
      (node (ref "U15") (pin "7") (pinfunction "~{PD}_7") (pintype "input+no_connect"))
    )
    (net (code "51") (name "unconnected-(U16-~{PD}-Pad7)") (class "Default")
      (node (ref "U16") (pin "7") (pinfunction "~{PD}_7") (pintype "input+no_connect"))
    )
    (net (code "52") (name "unconnected-(U17-~{PD}-Pad7)") (class "Default")
      (node (ref "U17") (pin "7") (pinfunction "~{PD}_7") (pintype "input+no_connect"))
    )
    (net (code "53") (name "unconnected-(U18-~{PD}-Pad7)") (class "Default")
      (node (ref "U18") (pin "7") (pinfunction "~{PD}_7") (pintype "input+no_connect"))
    )
  )
)
